# Mach_nap_HEALA.net
KiCad netlist of a schematic drawn in Altium Designer
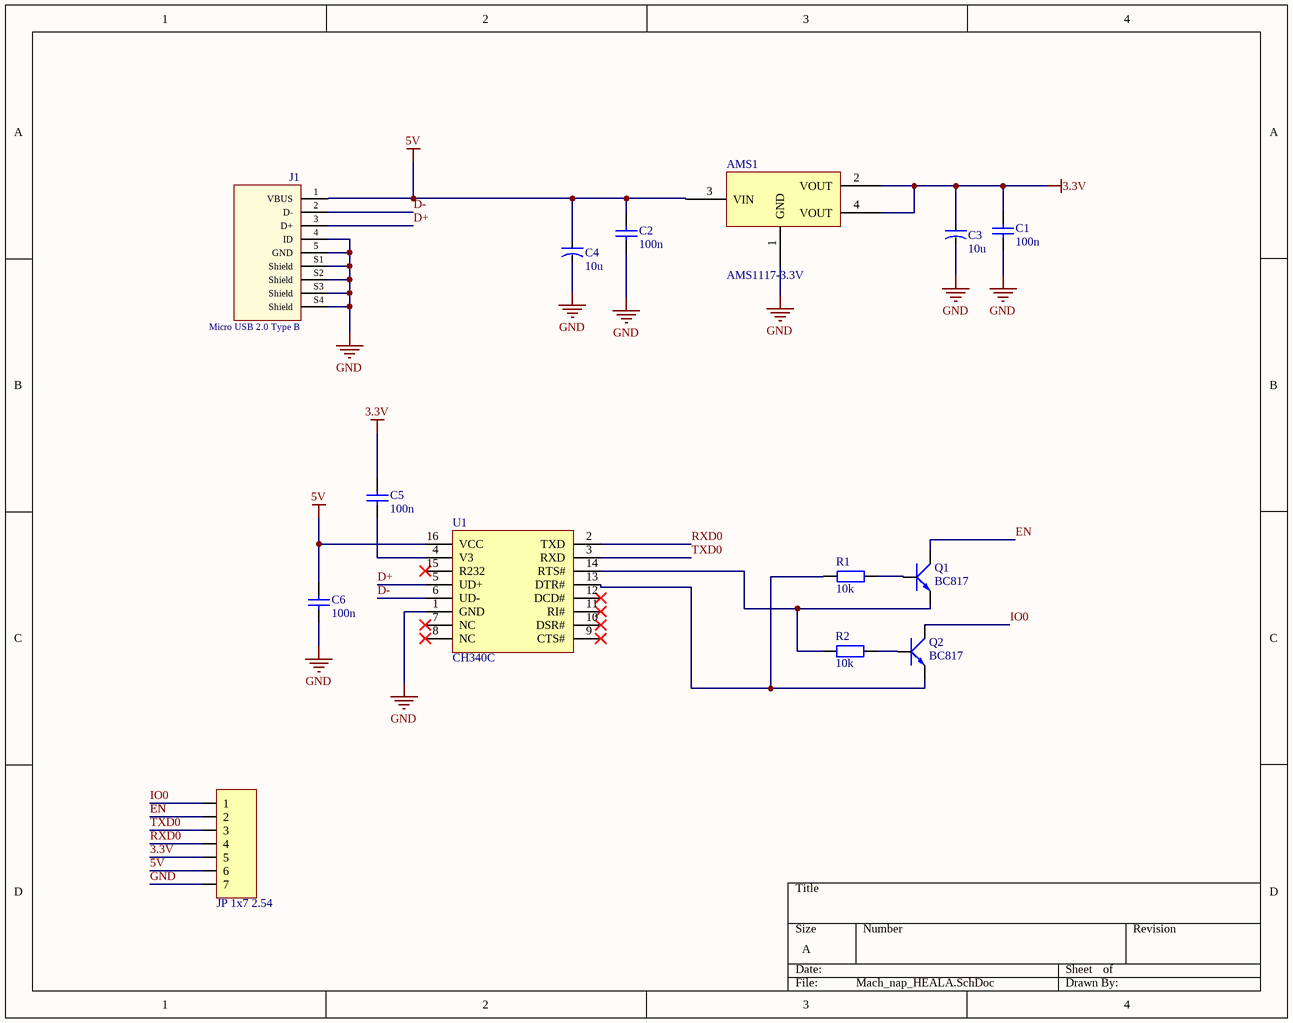
[diagram p0: Mach_nap_HEALA.SchDoc]

(export (version "E")
  (design (tool "Eeschema 10.0.6"))
  (components
    (comp (ref "AMS1")
      (value "AMS1117-3.3V")
      (footprint "SOT223")
      (description "Dán")
      (libsource (lib "IC") (part "AMS1117 SMD"))
    )
    (comp (ref "C1")
      (value "100n")
      (footprint "tu 1206")
      (description "Dán")
      (libsource (lib "Capacitor") (part "Tu 1206 106 16V 20%"))
    )
    (comp (ref "C2")
      (value "100n")
      (footprint "tu 1206")
      (description "Dán")
      (libsource (lib "Capacitor") (part "Tu 1206 106 16V 20%"))
    )
    (comp (ref "C3")
      (value "10u")
      (footprint "CAP-ALU-SMD-5x5.5x1.4")
      (description "Polarized Capacitor (Axial)")
      (fields (field (name "PUBLISHER") "Altium Limited"))
      (libsource (lib "Library") (part "CN-SMD"))
    )
    (comp (ref "C4")
      (value "10u")
      (footprint "CAP-ALU-SMD-5x5.5x1.4")
      (description "Polarized Capacitor (Axial)")
      (fields (field (name "PUBLISHER") "Altium Limited"))
      (libsource (lib "Library") (part "CN-SMD"))
    )
    (comp (ref "C5")
      (value "100n")
      (footprint "tu 1206")
      (description "Dán")
      (libsource (lib "Capacitor") (part "Tu 1206 106 16V 20%"))
    )
    (comp (ref "C6")
      (value "100n")
      (footprint "tu 1206")
      (description "Dán")
      (libsource (lib "Capacitor") (part "Tu 1206 106 16V 20%"))
    )
    (comp (ref "J1")
      (value "Micro USB 2.0 Type B")
      (footprint "629105136821")
      (description "Micro USB 2.0 Type B Horizontal SMT 5 Contacts WR-COM")
      (fields (field (name "PART NUMBER") "629105136821") (field (name "PUBLISHER") "Wurth Elektronik"))
      (libsource (lib "USB") (part "629105136821"))
    )
    (comp (ref "JP1")
      (value "JP 1x7 2.54")
      (footprint "JP 1x7 DT")
      (description "Cắm")
      (libsource (lib "Jump") (part "JP 1x7 2.54 Duc Thang"))
    )
    (comp (ref "Q1")
      (value "BC817")
      (footprint "SOT-23")
      (description "SOT-23 - C8658")
      (libsource (lib "TranFet") (part "Trans BC817"))
    )
    (comp (ref "Q2")
      (value "BC817")
      (footprint "SOT-23")
      (description "SOT-23 - C8658")
      (libsource (lib "TranFet") (part "Trans BC817"))
    )
    (comp (ref "R1")
      (value "10k")
      (footprint "tro smd 1206")
      (description "Dán")
      (libsource (lib "Resistor") (part "Tro 1206 5% 10k"))
    )
    (comp (ref "R2")
      (value "10k")
      (footprint "tro smd 1206")
      (description "Dán")
      (libsource (lib "Resistor") (part "Tro 1206 5% 10k"))
    )
    (comp (ref "U1")
      (value "CH340C")
      (footprint "SOIC16_50_284_25X90_SMT")
      (description "USB Bridge, USB to UART USB 2.0 UART Interface")
      (fields (field (name "MANUFACTURER") "Olimex"))
      (libsource (lib "IC") (part "CH340C"))
    )
  )
  (nets
    (net (code "1") (name "/D+") (class "Default")
      (node (ref "J1") (pin "3") (pinfunction "D+_3") (pintype "passive"))
      (node (ref "U1") (pin "5") (pinfunction "UD+_5") (pintype "passive"))
    )
    (net (code "2") (name "/D-") (class "Default")
      (node (ref "J1") (pin "2") (pinfunction "D-_2") (pintype "passive"))
      (node (ref "U1") (pin "6") (pinfunction "UD-_6") (pintype "passive"))
    )
    (net (code "3") (name "/EN") (class "Default")
      (node (ref "JP1") (pin "2") (pinfunction "2_2") (pintype "passive"))
      (node (ref "Q1") (pin "3") (pinfunction "C_3") (pintype "passive"))
    )
    (net (code "4") (name "/IO0") (class "Default")
      (node (ref "JP1") (pin "1") (pinfunction "1_1") (pintype "passive"))
      (node (ref "Q2") (pin "3") (pinfunction "C_3") (pintype "passive"))
    )
    (net (code "5") (name "/RXD0") (class "Default")
      (node (ref "JP1") (pin "4") (pinfunction "4_4") (pintype "passive"))
      (node (ref "U1") (pin "2") (pinfunction "TXD_2") (pintype "passive"))
    )
    (net (code "6") (name "/TXD0") (class "Default")
      (node (ref "JP1") (pin "3") (pinfunction "3_3") (pintype "passive"))
      (node (ref "U1") (pin "3") (pinfunction "RXD_3") (pintype "passive"))
    )
    (net (code "7") (name "3.3V") (class "Default")
      (node (ref "AMS1") (pin "2") (pinfunction "VOUT_2") (pintype "passive"))
      (node (ref "AMS1") (pin "4") (pinfunction "VOUT_4") (pintype "passive"))
      (node (ref "C1") (pin "1") (pinfunction "1_1") (pintype "passive"))
      (node (ref "C3") (pin "1") (pinfunction "1_1") (pintype "passive"))
      (node (ref "C5") (pin "1") (pinfunction "1_1") (pintype "passive"))
      (node (ref "JP1") (pin "5") (pinfunction "5_5") (pintype "passive"))
    )
    (net (code "8") (name "5V") (class "Default")
      (node (ref "AMS1") (pin "3") (pinfunction "VIN_3") (pintype "passive"))
      (node (ref "C2") (pin "1") (pinfunction "1_1") (pintype "passive"))
      (node (ref "C4") (pin "1") (pinfunction "1_1") (pintype "passive"))
      (node (ref "C6") (pin "1") (pinfunction "1_1") (pintype "passive"))
      (node (ref "J1") (pin "1") (pinfunction "VBUS_1") (pintype "passive"))
      (node (ref "JP1") (pin "6") (pinfunction "6_6") (pintype "passive"))
      (node (ref "U1") (pin "16") (pinfunction "VCC_16") (pintype "passive"))
    )
    (net (code "9") (name "GND") (class "Default")
      (node (ref "AMS1") (pin "1") (pinfunction "GND_1") (pintype "passive"))
      (node (ref "C1") (pin "2") (pinfunction "2_2") (pintype "passive"))
      (node (ref "C2") (pin "2") (pinfunction "2_2") (pintype "passive"))
      (node (ref "C3") (pin "2") (pinfunction "2_2") (pintype "passive"))
      (node (ref "C4") (pin "2") (pinfunction "2_2") (pintype "passive"))
      (node (ref "C6") (pin "2") (pinfunction "2_2") (pintype "passive"))
      (node (ref "J1") (pin "4") (pinfunction "ID_4") (pintype "passive"))
      (node (ref "J1") (pin "5") (pinfunction "GND_5") (pintype "passive"))
      (node (ref "J1") (pin "S1") (pinfunction "Shield_S1") (pintype "passive"))
      (node (ref "J1") (pin "S2") (pinfunction "Shield_S2") (pintype "passive"))
      (node (ref "J1") (pin "S3") (pinfunction "Shield_S3") (pintype "passive"))
      (node (ref "J1") (pin "S4") (pinfunction "Shield_S4") (pintype "passive"))
      (node (ref "JP1") (pin "7") (pinfunction "7_7") (pintype "passive"))
      (node (ref "U1") (pin "1") (pinfunction "GND_1") (pintype "passive"))
    )
    (net (code "10") (name "Net-(Q1-B)") (class "Default")
      (node (ref "Q1") (pin "1") (pinfunction "B_1") (pintype "passive"))
      (node (ref "R1") (pin "2") (pinfunction "2_2") (pintype "passive"))
    )
    (net (code "11") (name "Net-(Q1-E)") (class "Default")
      (node (ref "Q1") (pin "2") (pinfunction "E_2") (pintype "passive"))
      (node (ref "R2") (pin "1") (pinfunction "1_1") (pintype "passive"))
      (node (ref "U1") (pin "14") (pinfunction "RTS#_14") (pintype "passive"))
    )
    (net (code "12") (name "Net-(Q2-B)") (class "Default")
      (node (ref "Q2") (pin "1") (pinfunction "B_1") (pintype "passive"))
      (node (ref "R2") (pin "2") (pinfunction "2_2") (pintype "passive"))
    )
    (net (code "13") (name "Net-(Q2-E)") (class "Default")
      (node (ref "Q2") (pin "2") (pinfunction "E_2") (pintype "passive"))
      (node (ref "R1") (pin "1") (pinfunction "1_1") (pintype "passive"))
      (node (ref "U1") (pin "13") (pinfunction "DTR#_13") (pintype "passive"))
    )
    (net (code "14") (name "Net-(U1-V3)") (class "Default")
      (node (ref "C5") (pin "2") (pinfunction "2_2") (pintype "passive"))
      (node (ref "U1") (pin "4") (pinfunction "V3_4") (pintype "passive"))
    )
    (net (code "15") (name "unconnected-(U1-CTS#-Pad9)") (class "Default")
      (node (ref "U1") (pin "9") (pinfunction "CTS#_9") (pintype "passive+no_connect"))
    )
    (net (code "16") (name "unconnected-(U1-DCD#-Pad12)") (class "Default")
      (node (ref "U1") (pin "12") (pinfunction "DCD#_12") (pintype "passive+no_connect"))
    )
    (net (code "17") (name "unconnected-(U1-DSR#-Pad10)") (class "Default")
      (node (ref "U1") (pin "10") (pinfunction "DSR#_10") (pintype "passive+no_connect"))
    )
    (net (code "18") (name "unconnected-(U1-NC-Pad7)") (class "Default")
      (node (ref "U1") (pin "7") (pinfunction "NC_7") (pintype "passive+no_connect"))
    )
    (net (code "19") (name "unconnected-(U1-NC-Pad8)") (class "Default")
      (node (ref "U1") (pin "8") (pinfunction "NC_8") (pintype "passive+no_connect"))
    )
    (net (code "20") (name "unconnected-(U1-R232-Pad15)") (class "Default")
      (node (ref "U1") (pin "15") (pinfunction "R232_15") (pintype "passive+no_connect"))
    )
    (net (code "21") (name "unconnected-(U1-RI#-Pad11)") (class "Default")
      (node (ref "U1") (pin "11") (pinfunction "RI#_11") (pintype "passive+no_connect"))
    )
  )
)
